# sensors.net
KiCad netlist of a schematic drawn in Altium Designer
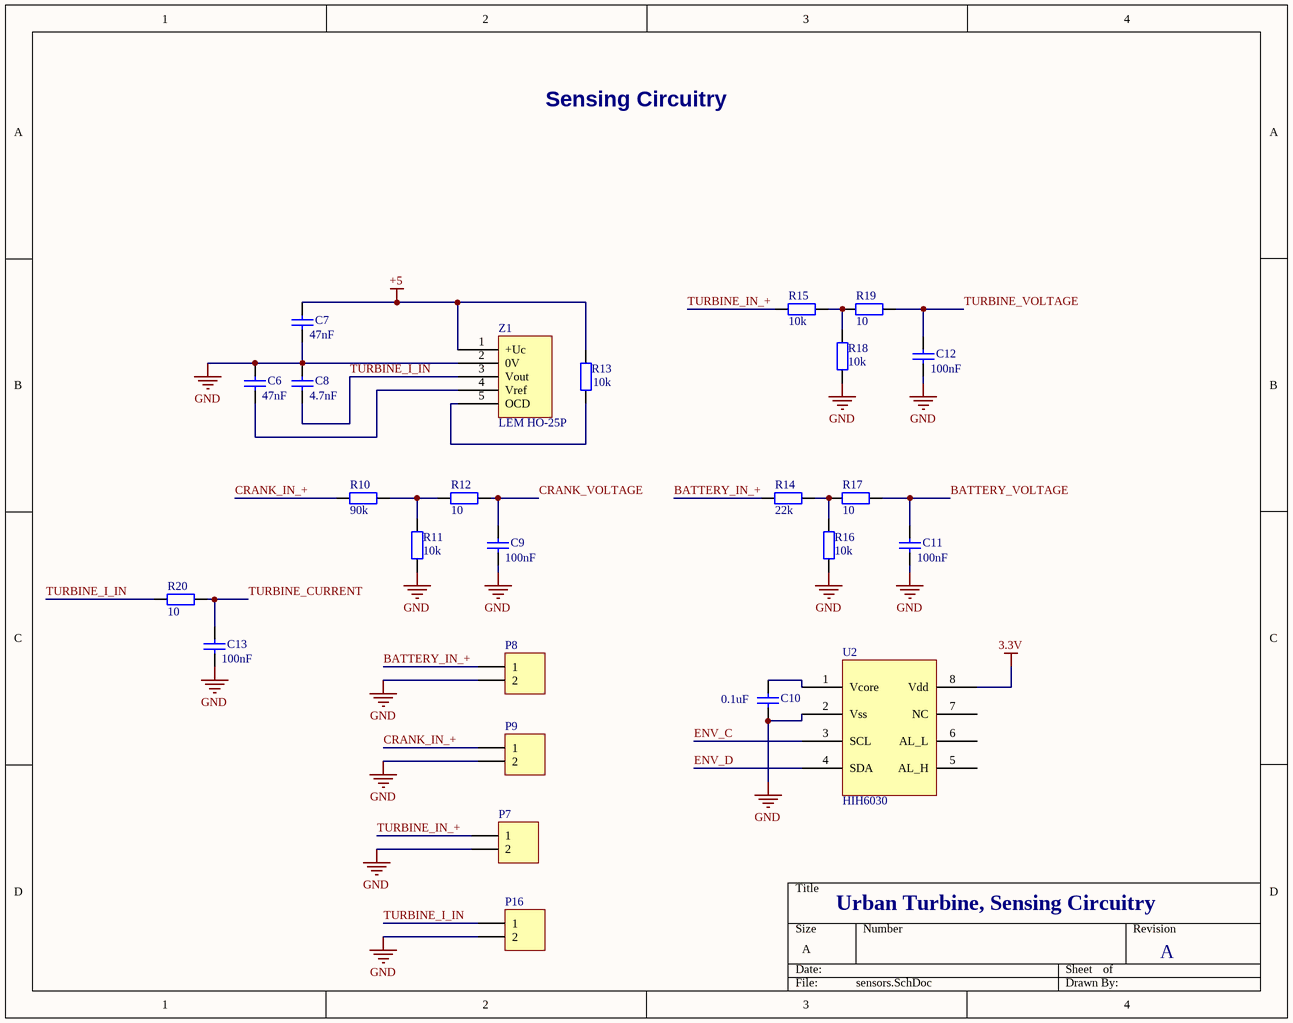
[diagram p0: sensors.SchDoc]

(export (version "E")
  (design (tool "Eeschema 10.0.6"))
  (components
    (comp (ref "C6")
      (value "47nF")
      (footprint "RAD-0.1")
      (description "Capacitor")
      (fields (field (name "Comment") "Cap") (field (name "PUBLISHER") "Altium Limited"))
      (libsource (lib "Miscellaneous Devices") (part "Cap"))
    )
    (comp (ref "C7")
      (value "47nF")
      (footprint "RAD-0.1")
      (description "Capacitor")
      (fields (field (name "Comment") "Cap") (field (name "PUBLISHER") "Altium Limited"))
      (libsource (lib "Miscellaneous Devices") (part "Cap"))
    )
    (comp (ref "C8")
      (value "4.7nF")
      (footprint "RAD-0.1")
      (description "Capacitor")
      (fields (field (name "Comment") "Cap") (field (name "PUBLISHER") "Altium Limited"))
      (libsource (lib "Miscellaneous Devices") (part "Cap"))
    )
    (comp (ref "C9")
      (value "100nF")
      (footprint "RAD-0.1")
      (description "Capacitor")
      (fields (field (name "Comment") "Cap") (field (name "PUBLISHER") "Altium Limited"))
      (libsource (lib "Miscellaneous Devices") (part "Cap"))
    )
    (comp (ref "C10")
      (value "0.1uF")
      (footprint "RAD-0.1")
      (description "Capacitor")
      (fields (field (name "Comment") "p") (field (name "PUBLISHER") "Altium Limited"))
      (libsource (lib "Miscellaneous Devices") (part "Cap"))
    )
    (comp (ref "C11")
      (value "100nF")
      (footprint "RAD-0.1")
      (description "Capacitor")
      (fields (field (name "Comment") "Cap") (field (name "PUBLISHER") "Altium Limited"))
      (libsource (lib "Miscellaneous Devices") (part "Cap"))
    )
    (comp (ref "C12")
      (value "100nF")
      (footprint "RAD-0.1")
      (description "Capacitor")
      (fields (field (name "Comment") "Cap") (field (name "PUBLISHER") "Altium Limited"))
      (libsource (lib "Miscellaneous Devices") (part "Cap"))
    )
    (comp (ref "C13")
      (value "100nF")
      (footprint "RAD-0.1")
      (description "Capacitor")
      (fields (field (name "Comment") "Cap") (field (name "PUBLISHER") "Altium Limited"))
      (libsource (lib "Miscellaneous Devices") (part "Cap"))
    )
    (comp (ref "P7")
      (value "~")
      (footprint "HDR1X2")
      (description "Header, 2-Pin")
      (fields (field (name "PUBLISHER") "Altium Limited"))
      (libsource (lib "Miscellaneous Connectors") (part "Header 2"))
    )
    (comp (ref "P8")
      (value "~")
      (footprint "HDR1X2")
      (description "Header, 2-Pin")
      (fields (field (name "PUBLISHER") "Altium Limited"))
      (libsource (lib "Miscellaneous Connectors") (part "Header 2"))
    )
    (comp (ref "P9")
      (value "~")
      (footprint "HDR1X2")
      (description "Header, 2-Pin")
      (fields (field (name "PUBLISHER") "Altium Limited"))
      (libsource (lib "Miscellaneous Connectors") (part "Header 2"))
    )
    (comp (ref "P16")
      (value "~")
      (footprint "HDR1X2")
      (description "Header, 2-Pin")
      (fields (field (name "PUBLISHER") "Altium Limited"))
      (libsource (lib "Miscellaneous Connectors") (part "Header 2"))
    )
    (comp (ref "R10")
      (value "90k")
      (footprint "AXIAL-0.4")
      (description "Resistor")
      (fields (field (name "Comment") "Res2") (field (name "PUBLISHER") "Altium Limited"))
      (libsource (lib "") (part "Res2_1"))
    )
    (comp (ref "R11")
      (value "10k")
      (footprint "AXIAL-0.4")
      (description "Resistor")
      (fields (field (name "Comment") "Res2") (field (name "PUBLISHER") "Altium Limited"))
      (libsource (lib "Miscellaneous Devices") (part "Res2"))
    )
    (comp (ref "R12")
      (value "10")
      (footprint "AXIAL-0.4")
      (description "Resistor")
      (fields (field (name "Comment") "Res2") (field (name "PUBLISHER") "Altium Limited"))
      (libsource (lib "") (part "Res2_1"))
    )
    (comp (ref "R13")
      (value "10k")
      (footprint "AXIAL-0.4")
      (description "Resistor")
      (fields (field (name "Comment") "Res2") (field (name "PUBLISHER") "Altium Limited"))
      (libsource (lib "") (part "Res2_2"))
    )
    (comp (ref "R14")
      (value "22k")
      (footprint "AXIAL-0.4")
      (description "Resistor")
      (fields (field (name "Comment") "Res2") (field (name "PUBLISHER") "Altium Limited"))
      (libsource (lib "") (part "Res2_1"))
    )
    (comp (ref "R15")
      (value "10k")
      (footprint "AXIAL-0.4")
      (description "Resistor")
      (fields (field (name "Comment") "Res2") (field (name "PUBLISHER") "Altium Limited"))
      (libsource (lib "") (part "Res2_1"))
    )
    (comp (ref "R16")
      (value "10k")
      (footprint "AXIAL-0.4")
      (description "Resistor")
      (fields (field (name "Comment") "Res2") (field (name "PUBLISHER") "Altium Limited"))
      (libsource (lib "Miscellaneous Devices") (part "Res2"))
    )
    (comp (ref "R17")
      (value "10")
      (footprint "AXIAL-0.4")
      (description "Resistor")
      (fields (field (name "Comment") "Res2") (field (name "PUBLISHER") "Altium Limited"))
      (libsource (lib "") (part "Res2_1"))
    )
    (comp (ref "R18")
      (value "10k")
      (footprint "AXIAL-0.4")
      (description "Resistor")
      (fields (field (name "Comment") "Res2") (field (name "PUBLISHER") "Altium Limited"))
      (libsource (lib "Miscellaneous Devices") (part "Res2"))
    )
    (comp (ref "R19")
      (value "10")
      (footprint "AXIAL-0.4")
      (description "Resistor")
      (fields (field (name "Comment") "Res2") (field (name "PUBLISHER") "Altium Limited"))
      (libsource (lib "") (part "Res2_1"))
    )
    (comp (ref "R20")
      (value "10")
      (footprint "AXIAL-0.4")
      (description "Resistor")
      (fields (field (name "Comment") "Res2") (field (name "PUBLISHER") "Altium Limited"))
      (libsource (lib "") (part "Res2_1"))
    )
    (comp (ref "U2")
      (value "HIH6030")
      (footprint "HIH6300")
      (description "Temp/Humidity Sensor")
      (libsource (lib "urbanturbine") (part "HIH6030"))
    )
    (comp (ref "Z1")
      (value "LEM HO-25P")
      (footprint "HO-25")
      (description "Hall Effect Current Sensor")
      (libsource (lib "urbanturbine") (part "LEM HO-25P"))
    )
  )
  (nets
    (net (code "1") (name "+5") (class "Default")
      (node (ref "C7") (pin "2") (pinfunction "2_2") (pintype "passive"))
      (node (ref "R13") (pin "2") (pinfunction "2_2") (pintype "passive"))
      (node (ref "Z1") (pin "1") (pinfunction "+Uc_1") (pintype "passive"))
    )
    (net (code "2") (name "/BATTERY_IN_+") (class "Default")
      (node (ref "P8") (pin "1") (pinfunction "1_1") (pintype "passive"))
      (node (ref "R14") (pin "2") (pinfunction "2_2") (pintype "passive"))
    )
    (net (code "3") (name "/BATTERY_VOLTAGE") (class "Default")
      (node (ref "C11") (pin "2") (pinfunction "2_2") (pintype "passive"))
      (node (ref "R17") (pin "1") (pinfunction "1_1") (pintype "passive"))
    )
    (net (code "4") (name "/CRANK_IN_+") (class "Default")
      (node (ref "P9") (pin "1") (pinfunction "1_1") (pintype "passive"))
      (node (ref "R10") (pin "2") (pinfunction "2_2") (pintype "passive"))
    )
    (net (code "5") (name "/CRANK_VOLTAGE") (class "Default")
      (node (ref "C9") (pin "2") (pinfunction "2_2") (pintype "passive"))
      (node (ref "R12") (pin "1") (pinfunction "1_1") (pintype "passive"))
    )
    (net (code "6") (name "/ENV_C") (class "Default")
      (node (ref "U2") (pin "3") (pinfunction "SCL_3") (pintype "passive"))
    )
    (net (code "7") (name "/ENV_D") (class "Default")
      (node (ref "U2") (pin "4") (pinfunction "SDA_4") (pintype "passive"))
    )
    (net (code "8") (name "/TURBINE_CURRENT") (class "Default")
      (node (ref "C13") (pin "2") (pinfunction "2_2") (pintype "passive"))
      (node (ref "R20") (pin "1") (pinfunction "1_1") (pintype "passive"))
    )
    (net (code "9") (name "/TURBINE_IN_+") (class "Default")
      (node (ref "P7") (pin "1") (pinfunction "1_1") (pintype "passive"))
      (node (ref "R15") (pin "2") (pinfunction "2_2") (pintype "passive"))
    )
    (net (code "10") (name "/TURBINE_I_IN") (class "Default")
      (node (ref "C8") (pin "1") (pinfunction "1_1") (pintype "passive"))
      (node (ref "P16") (pin "1") (pinfunction "1_1") (pintype "passive"))
      (node (ref "R20") (pin "2") (pinfunction "2_2") (pintype "passive"))
      (node (ref "Z1") (pin "3") (pinfunction "Vout_3") (pintype "passive"))
    )
    (net (code "11") (name "/TURBINE_VOLTAGE") (class "Default")
      (node (ref "C12") (pin "2") (pinfunction "2_2") (pintype "passive"))
      (node (ref "R19") (pin "1") (pinfunction "1_1") (pintype "passive"))
    )
    (net (code "12") (name "3.3V") (class "Default")
      (node (ref "U2") (pin "8") (pinfunction "Vdd_8") (pintype "passive"))
    )
    (net (code "13") (name "GND") (class "Default")
      (node (ref "C10") (pin "1") (pinfunction "1_1") (pintype "passive"))
      (node (ref "C11") (pin "1") (pinfunction "1_1") (pintype "passive"))
      (node (ref "C12") (pin "1") (pinfunction "1_1") (pintype "passive"))
      (node (ref "C13") (pin "1") (pinfunction "1_1") (pintype "passive"))
      (node (ref "C6") (pin "2") (pinfunction "2_2") (pintype "passive"))
      (node (ref "C7") (pin "1") (pinfunction "1_1") (pintype "passive"))
      (node (ref "C8") (pin "2") (pinfunction "2_2") (pintype "passive"))
      (node (ref "C9") (pin "1") (pinfunction "1_1") (pintype "passive"))
      (node (ref "P16") (pin "2") (pinfunction "2_2") (pintype "passive"))
      (node (ref "P7") (pin "2") (pinfunction "2_2") (pintype "passive"))
      (node (ref "P8") (pin "2") (pinfunction "2_2") (pintype "passive"))
      (node (ref "P9") (pin "2") (pinfunction "2_2") (pintype "passive"))
      (node (ref "R11") (pin "2") (pinfunction "2_2") (pintype "passive"))
      (node (ref "R16") (pin "2") (pinfunction "2_2") (pintype "passive"))
      (node (ref "R18") (pin "2") (pinfunction "2_2") (pintype "passive"))
      (node (ref "U2") (pin "2") (pinfunction "Vss_2") (pintype "passive"))
      (node (ref "Z1") (pin "2") (pinfunction "0V_2") (pintype "passive"))
    )
    (net (code "14") (name "Net-(R10-Pad1)") (class "Default")
      (node (ref "R10") (pin "1") (pinfunction "1_1") (pintype "passive"))
      (node (ref "R11") (pin "1") (pinfunction "1_1") (pintype "passive"))
      (node (ref "R12") (pin "2") (pinfunction "2_2") (pintype "passive"))
    )
    (net (code "15") (name "Net-(R14-Pad1)") (class "Default")
      (node (ref "R14") (pin "1") (pinfunction "1_1") (pintype "passive"))
      (node (ref "R16") (pin "1") (pinfunction "1_1") (pintype "passive"))
      (node (ref "R17") (pin "2") (pinfunction "2_2") (pintype "passive"))
    )
    (net (code "16") (name "Net-(R15-Pad1)") (class "Default")
      (node (ref "R15") (pin "1") (pinfunction "1_1") (pintype "passive"))
      (node (ref "R18") (pin "1") (pinfunction "1_1") (pintype "passive"))
      (node (ref "R19") (pin "2") (pinfunction "2_2") (pintype "passive"))
    )
    (net (code "17") (name "Net-(U2-Vcore)") (class "Default")
      (node (ref "C10") (pin "2") (pinfunction "2_2") (pintype "passive"))
      (node (ref "U2") (pin "1") (pinfunction "Vcore_1") (pintype "passive"))
    )
    (net (code "18") (name "Net-(Z1-OCD)") (class "Default")
      (node (ref "R13") (pin "1") (pinfunction "1_1") (pintype "passive"))
      (node (ref "Z1") (pin "5") (pinfunction "OCD_5") (pintype "passive"))
    )
    (net (code "19") (name "Net-(Z1-Vref)") (class "Default")
      (node (ref "C6") (pin "1") (pinfunction "1_1") (pintype "passive"))
      (node (ref "Z1") (pin "4") (pinfunction "Vref_4") (pintype "passive"))
    )
    (net (code "20") (name "unconnected-(U2-AL_H-Pad5)") (class "Default")
      (node (ref "U2") (pin "5") (pinfunction "AL_H_5") (pintype "passive"))
    )
    (net (code "21") (name "unconnected-(U2-AL_L-Pad6)") (class "Default")
      (node (ref "U2") (pin "6") (pinfunction "AL_L_6") (pintype "passive"))
    )
    (net (code "22") (name "unconnected-(U2-NC-Pad7)") (class "Default")
      (node (ref "U2") (pin "7") (pinfunction "NC_7") (pintype "passive"))
    )
  )
)
